# Programmer.net
KiCad netlist of a schematic drawn in Altium Designer
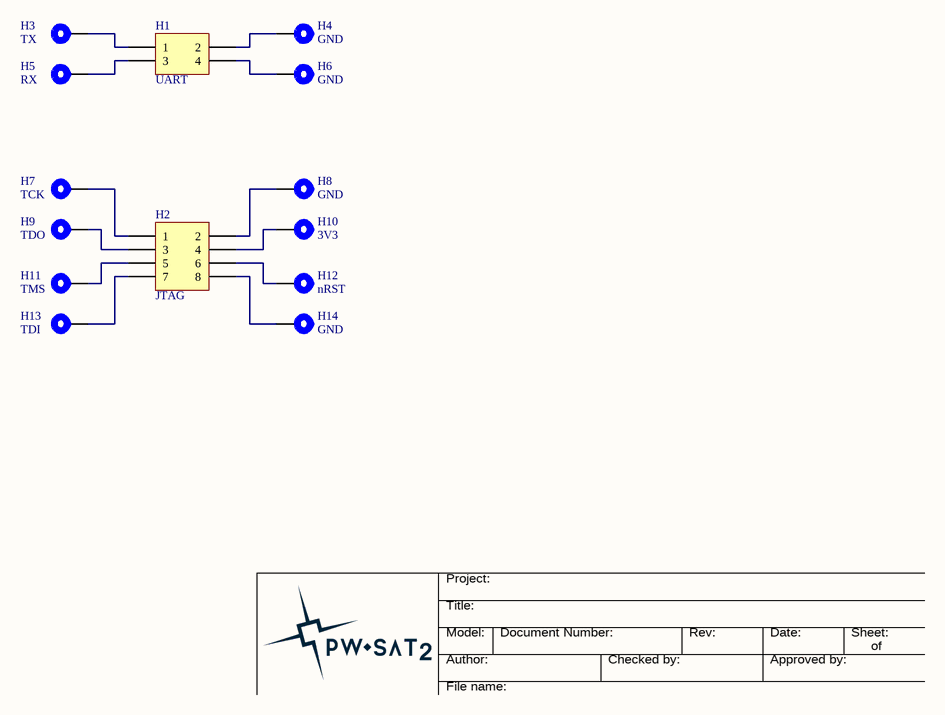
[diagram p0: Programmer.SchDoc]

(export (version "E")
  (design (tool "Eeschema 10.0.6"))
  (components
    (comp (ref "H1")
      (value "UART")
      (footprint "Connfly_DS1065-03-2X2")
      (description "Header, 2-Pin, Dual row")
      (fields (field (name "PUBLISHER") "Altium Limited"))
      (libsource (lib "connectors_printed-circuit-board") (part "Header 2X2"))
    )
    (comp (ref "H2")
      (value "JTAG")
      (footprint "Connfly_DS1065-03-2X4")
      (description "Header, 4-Pin, Dual row")
      (fields (field (name "PUBLISHER") "Altium Limited"))
      (libsource (lib "connectors_printed-circuit-board") (part "Header 4X2"))
    )
    (comp (ref "H3")
      (value "TX")
      (footprint "Wire_AWG-30")
      (description "An AWG-30 wire solder point.")
      (libsource (lib "connectors_printed-circuit-board") (part "Wire_AWG-30"))
    )
    (comp (ref "H4")
      (value "GND")
      (footprint "Wire_AWG-30")
      (description "An AWG-30 wire solder point.")
      (libsource (lib "connectors_printed-circuit-board") (part "Wire_AWG-30"))
    )
    (comp (ref "H5")
      (value "RX")
      (footprint "Wire_AWG-30")
      (description "An AWG-30 wire solder point.")
      (libsource (lib "connectors_printed-circuit-board") (part "Wire_AWG-30"))
    )
    (comp (ref "H6")
      (value "GND")
      (footprint "Wire_AWG-30")
      (description "An AWG-30 wire solder point.")
      (libsource (lib "connectors_printed-circuit-board") (part "Wire_AWG-30"))
    )
    (comp (ref "H7")
      (value "TCK")
      (footprint "Wire_AWG-30")
      (description "An AWG-30 wire solder point.")
      (libsource (lib "connectors_printed-circuit-board") (part "Wire_AWG-30"))
    )
    (comp (ref "H8")
      (value "GND")
      (footprint "Wire_AWG-30")
      (description "An AWG-30 wire solder point.")
      (libsource (lib "connectors_printed-circuit-board") (part "Wire_AWG-30"))
    )
    (comp (ref "H9")
      (value "TDO")
      (footprint "Wire_AWG-30")
      (description "An AWG-30 wire solder point.")
      (libsource (lib "connectors_printed-circuit-board") (part "Wire_AWG-30"))
    )
    (comp (ref "H10")
      (value "3V3")
      (footprint "Wire_AWG-30")
      (description "An AWG-30 wire solder point.")
      (libsource (lib "connectors_printed-circuit-board") (part "Wire_AWG-30"))
    )
    (comp (ref "H11")
      (value "TMS")
      (footprint "Wire_AWG-30")
      (description "An AWG-30 wire solder point.")
      (libsource (lib "connectors_printed-circuit-board") (part "Wire_AWG-30"))
    )
    (comp (ref "H12")
      (value "nRST")
      (footprint "Wire_AWG-30")
      (description "An AWG-30 wire solder point.")
      (libsource (lib "connectors_printed-circuit-board") (part "Wire_AWG-30"))
    )
    (comp (ref "H13")
      (value "TDI")
      (footprint "Wire_AWG-30")
      (description "An AWG-30 wire solder point.")
      (libsource (lib "connectors_printed-circuit-board") (part "Wire_AWG-30"))
    )
    (comp (ref "H14")
      (value "GND")
      (footprint "Wire_AWG-30")
      (description "An AWG-30 wire solder point.")
      (libsource (lib "connectors_printed-circuit-board") (part "Wire_AWG-30"))
    )
  )
  (nets
    (net (code "1") (name "Net-(H1-Pad1)") (class "Default")
      (node (ref "H1") (pin "1") (pinfunction "1_1") (pintype "passive"))
      (node (ref "H3") (pin "1") (pinfunction "1_1") (pintype "passive"))
    )
    (net (code "2") (name "Net-(H1-Pad2)") (class "Default")
      (node (ref "H1") (pin "2") (pinfunction "2_2") (pintype "passive"))
      (node (ref "H4") (pin "1") (pinfunction "1_1") (pintype "passive"))
    )
    (net (code "3") (name "Net-(H1-Pad3)") (class "Default")
      (node (ref "H1") (pin "3") (pinfunction "3_3") (pintype "passive"))
      (node (ref "H5") (pin "1") (pinfunction "1_1") (pintype "passive"))
    )
    (net (code "4") (name "Net-(H1-Pad4)") (class "Default")
      (node (ref "H1") (pin "4") (pinfunction "4_4") (pintype "passive"))
      (node (ref "H6") (pin "1") (pinfunction "1_1") (pintype "passive"))
    )
    (net (code "5") (name "Net-(H2-Pad1)") (class "Default")
      (node (ref "H2") (pin "1") (pinfunction "1_1") (pintype "passive"))
      (node (ref "H7") (pin "1") (pinfunction "1_1") (pintype "passive"))
    )
    (net (code "6") (name "Net-(H2-Pad2)") (class "Default")
      (node (ref "H2") (pin "2") (pinfunction "2_2") (pintype "passive"))
      (node (ref "H8") (pin "1") (pinfunction "1_1") (pintype "passive"))
    )
    (net (code "7") (name "Net-(H2-Pad3)") (class "Default")
      (node (ref "H2") (pin "3") (pinfunction "3_3") (pintype "passive"))
      (node (ref "H9") (pin "1") (pinfunction "1_1") (pintype "passive"))
    )
    (net (code "8") (name "Net-(H10-Pad1)") (class "Default")
      (node (ref "H10") (pin "1") (pinfunction "1_1") (pintype "passive"))
      (node (ref "H2") (pin "4") (pinfunction "4_4") (pintype "passive"))
    )
    (net (code "9") (name "Net-(H11-Pad1)") (class "Default")
      (node (ref "H11") (pin "1") (pinfunction "1_1") (pintype "passive"))
      (node (ref "H2") (pin "5") (pinfunction "5_5") (pintype "passive"))
    )
    (net (code "10") (name "Net-(H12-Pad1)") (class "Default")
      (node (ref "H12") (pin "1") (pinfunction "1_1") (pintype "passive"))
      (node (ref "H2") (pin "6") (pinfunction "6_6") (pintype "passive"))
    )
    (net (code "11") (name "Net-(H13-Pad1)") (class "Default")
      (node (ref "H13") (pin "1") (pinfunction "1_1") (pintype "passive"))
      (node (ref "H2") (pin "7") (pinfunction "7_7") (pintype "passive"))
    )
    (net (code "12") (name "Net-(H14-Pad1)") (class "Default")
      (node (ref "H14") (pin "1") (pinfunction "1_1") (pintype "passive"))
      (node (ref "H2") (pin "8") (pinfunction "8_8") (pintype "passive"))
    )
  )
)
